# FlatFlexPSensorLongerACF.net
KiCad netlist of a schematic drawn in EAGLE
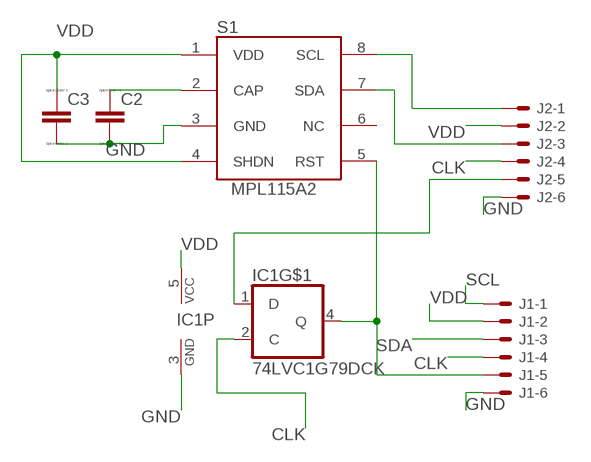
[diagram p0: schematic, sheet 1]

(export (version "E")
  (design (tool "Eeschema 10.0.6"))
  (components
    (comp (ref "C2")
      (value "CC0402")
      (footprint "eagle-import:C0402")
      (libsource (lib "eagle-import") (part "CC0402"))
    )
    (comp (ref "C3")
      (value "CC0402")
      (footprint "eagle-import:C0402")
      (libsource (lib "eagle-import") (part "CC0402"))
    )
    (comp (ref "IC1")
      (value "74LVC1G79DCK")
      (footprint "eagle-import:SC70-5")
      (libsource (lib "eagle-import") (part "741G79DCKLVC"))
    )
    (comp (ref "J1")
      (value "XF2L-0625-1")
      (footprint "eagle-import:XF2L-0625-1")
      (fields (field (name "MF") "OMRON COMPONENTS USA"))
      (libsource (lib "eagle-import") (part "XF2-06?25-1L"))
    )
    (comp (ref "J2")
      (value "XF2L-0625-1")
      (footprint "eagle-import:XF2L-0625-1")
      (fields (field (name "MF") "OMRON COMPONENTS USA"))
      (libsource (lib "eagle-import") (part "XF2-06?25-1L"))
    )
    (comp (ref "S1")
      (value "MPL115A2")
      (footprint "eagle-import:LGA8")
      (libsource (lib "eagle-import") (part "MPL115A2"))
    )
  )
  (nets
    (net (code "1") (name "/CLK") (class "Default")
      (node (ref "IC1") (pin "2") (pinfunction "C_2") (pintype "input"))
      (node (ref "J1") (pin "4") (pinfunction "MS_4") (pintype "passive"))
      (node (ref "J2") (pin "4") (pinfunction "MS_4") (pintype "passive"))
    )
    (net (code "2") (name "/GND") (class "Default")
      (node (ref "C2") (pin "2") (pinfunction "2_2") (pintype "passive"))
      (node (ref "C3") (pin "2") (pinfunction "2_2") (pintype "passive"))
      (node (ref "IC1") (pin "3") (pinfunction "GND_3") (pintype "power_in"))
      (node (ref "J1") (pin "6") (pinfunction "MS_6") (pintype "passive"))
      (node (ref "J2") (pin "6") (pinfunction "MS_6") (pintype "passive"))
      (node (ref "S1") (pin "3") (pinfunction "GND_3") (pintype "bidirectional"))
    )
    (net (code "3") (name "/SCL") (class "Default")
      (node (ref "J1") (pin "1") (pinfunction "MS_1") (pintype "passive"))
      (node (ref "J2") (pin "1") (pinfunction "MS_1") (pintype "passive"))
      (node (ref "S1") (pin "8") (pinfunction "SCL_8") (pintype "bidirectional"))
    )
    (net (code "4") (name "/SDA") (class "Default")
      (node (ref "J1") (pin "3") (pinfunction "MS_3") (pintype "passive"))
      (node (ref "J2") (pin "3") (pinfunction "MS_3") (pintype "passive"))
      (node (ref "S1") (pin "7") (pinfunction "SDA_7") (pintype "bidirectional"))
    )
    (net (code "5") (name "/VDD") (class "Default")
      (node (ref "C3") (pin "1") (pinfunction "1_1") (pintype "passive"))
      (node (ref "IC1") (pin "5") (pinfunction "VCC_5") (pintype "power_in"))
      (node (ref "J1") (pin "2") (pinfunction "MS_2") (pintype "passive"))
      (node (ref "J2") (pin "2") (pinfunction "MS_2") (pintype "passive"))
      (node (ref "S1") (pin "1") (pinfunction "VDD_1") (pintype "bidirectional"))
      (node (ref "S1") (pin "4") (pinfunction "SHDN_4") (pintype "bidirectional"))
    )
    (net (code "6") (name "Net-(IC1A-D)") (class "Default")
      (node (ref "IC1") (pin "1") (pinfunction "D_1") (pintype "input"))
      (node (ref "J2") (pin "5") (pinfunction "MS_5") (pintype "passive"))
    )
    (net (code "7") (name "Net-(IC1A-Q)") (class "Default")
      (node (ref "IC1") (pin "4") (pinfunction "Q_4") (pintype "output"))
      (node (ref "J1") (pin "5") (pinfunction "MS_5") (pintype "passive"))
      (node (ref "S1") (pin "5") (pinfunction "RST_5") (pintype "bidirectional"))
    )
    (net (code "8") (name "Net-(S1-CAP)") (class "Default")
      (node (ref "C2") (pin "1") (pinfunction "1_1") (pintype "passive"))
      (node (ref "S1") (pin "2") (pinfunction "CAP_2") (pintype "bidirectional"))
    )
    (net (code "9") (name "unconnected-(S1-NC-Pad6)") (class "Default")
      (node (ref "S1") (pin "6") (pinfunction "NC_6") (pintype "bidirectional"))
    )
  )
)
